# Class_D_Audio_Amplifier_on_TPA3255_ChipD.net
KiCad netlist of a schematic drawn in EasyEDA
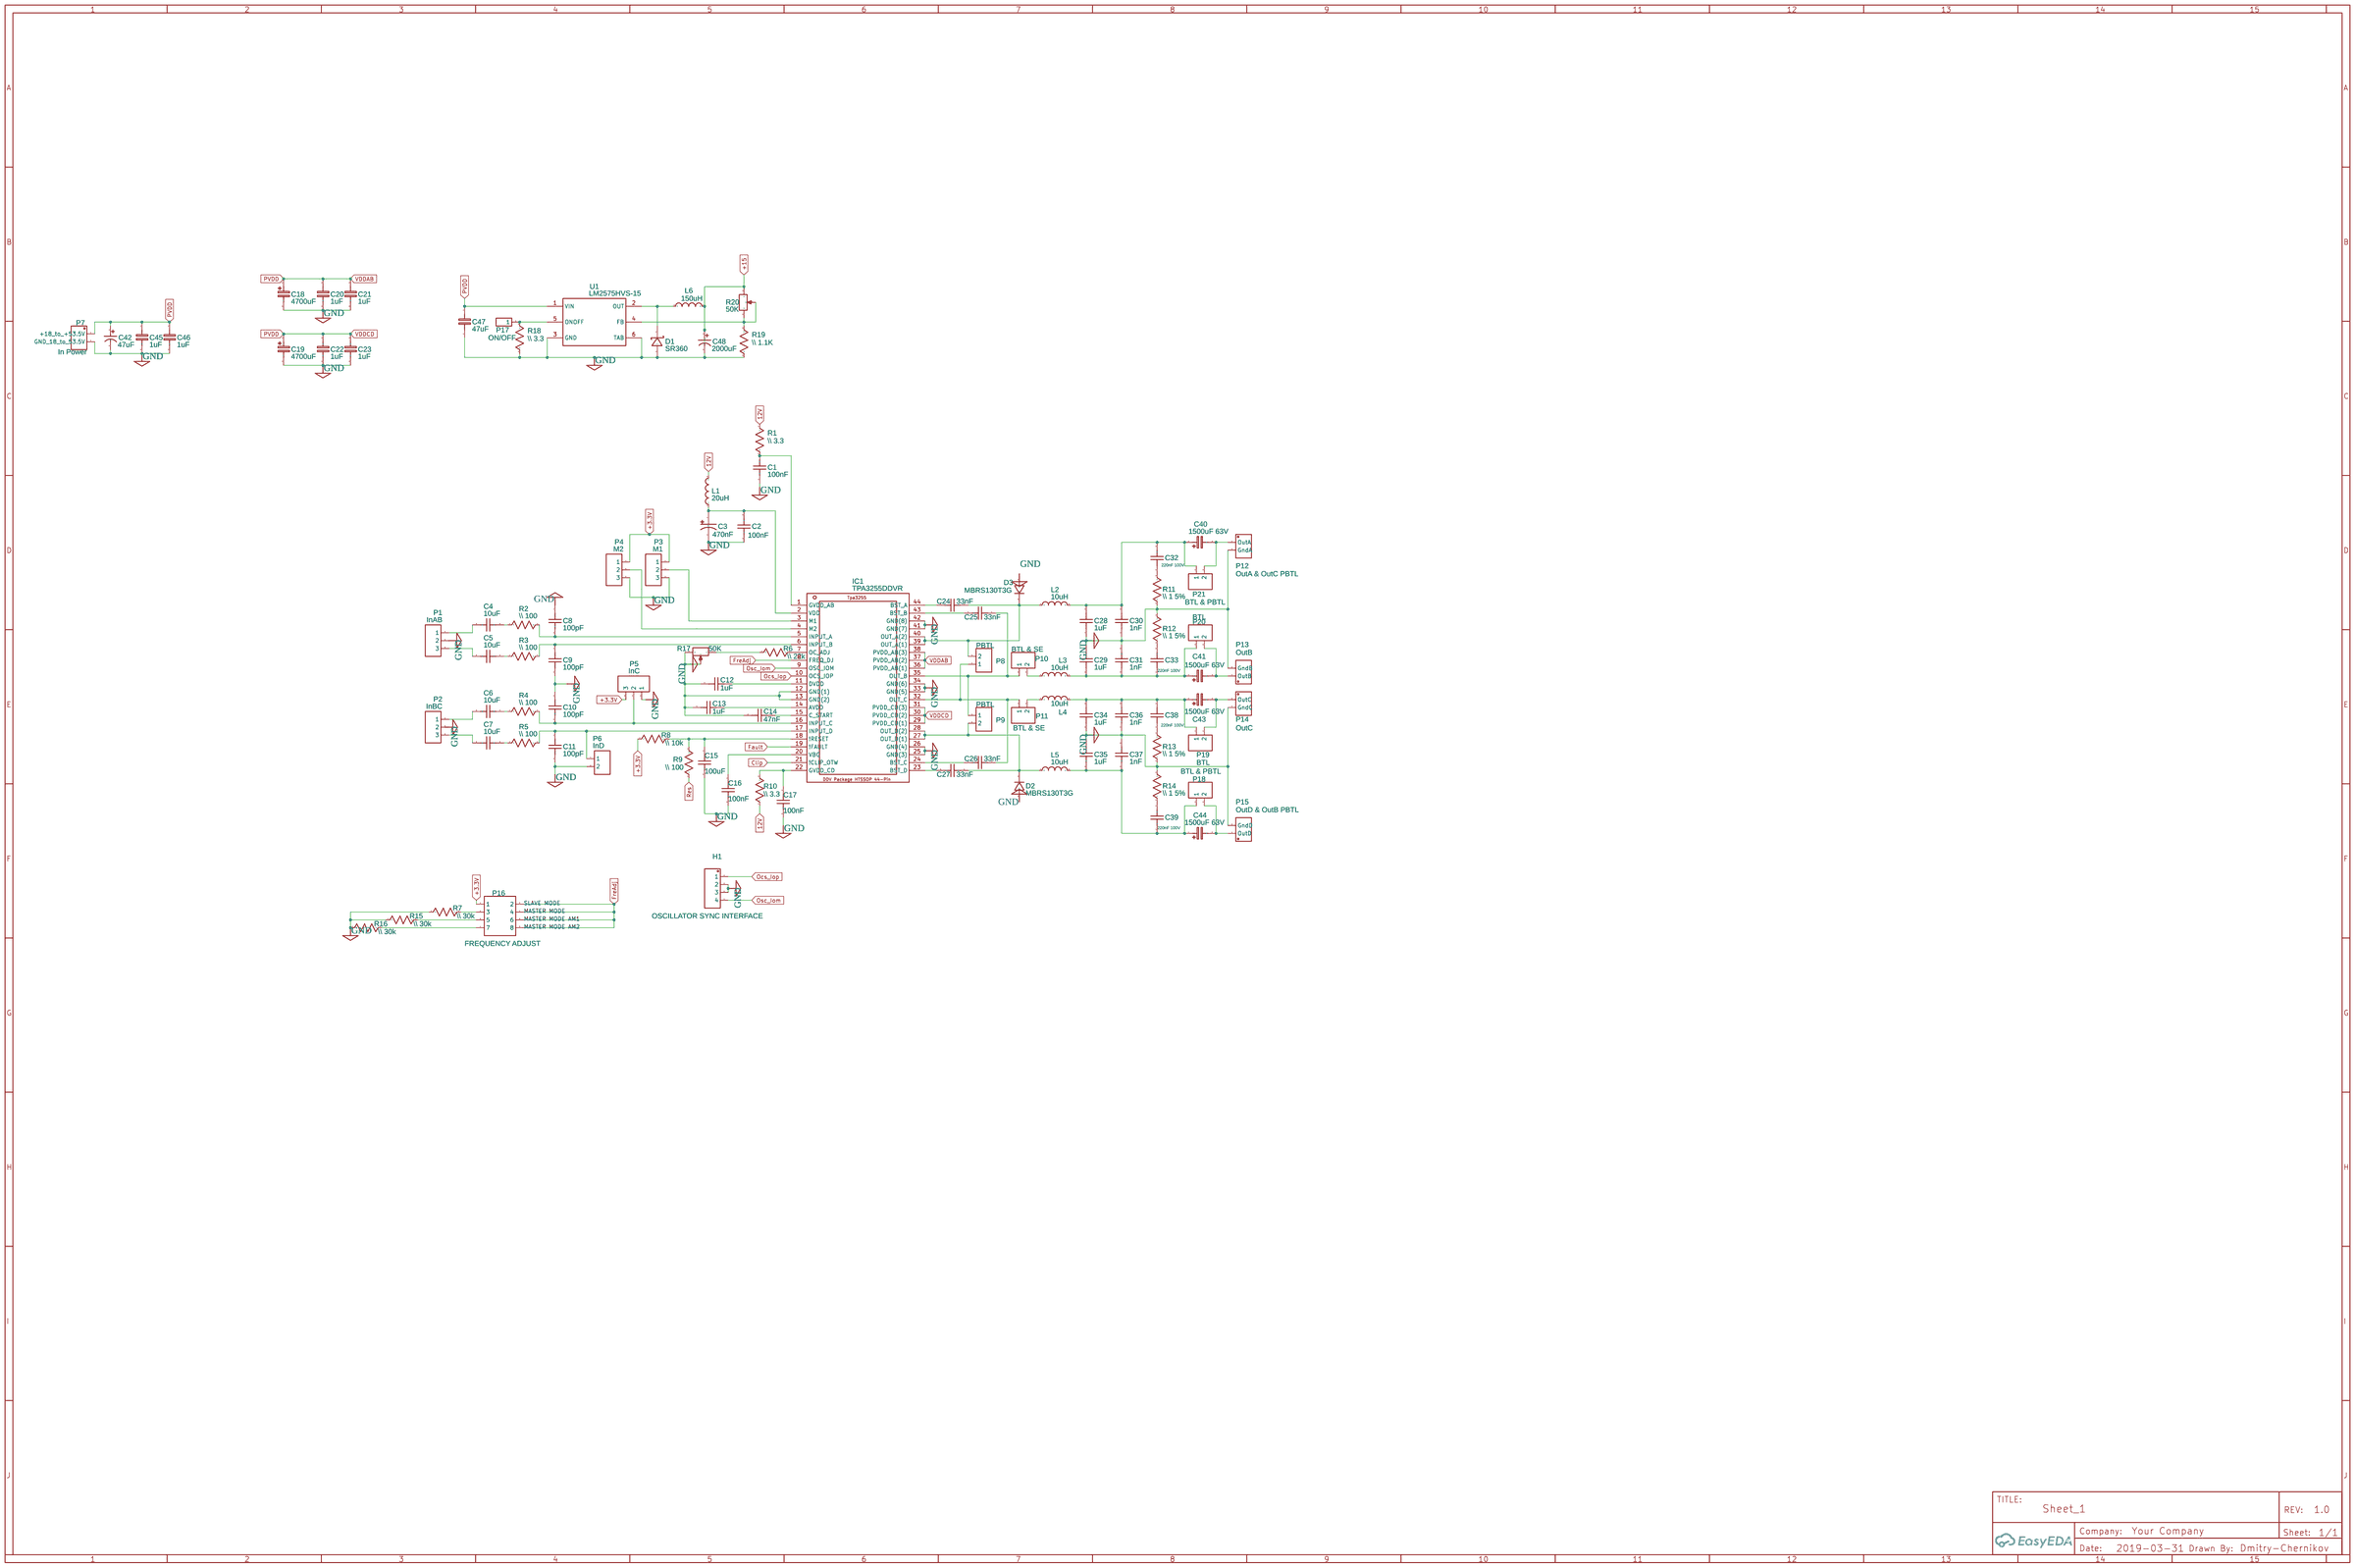
[diagram p0: schematic sheet]

(export (version "E")
  (design (tool "Eeschema 10.0.6"))
  (components
    (comp (ref "C1")
      (value "100nF")
      (fields (field (name "BOM_Manufacturer Part") "?"))
      (libsource (lib "") (part "Cap_RAD-0.2_US_1"))
    )
    (comp (ref "C2")
      (value "100nF")
      (fields (field (name "BOM_Manufacturer Part") "?"))
      (libsource (lib "") (part "Cap_RAD-0.2_US_1"))
    )
    (comp (ref "C3")
      (value "470nF")
      (fields (field (name "BOM_Manufacturer Part") "?"))
      (libsource (lib "") (part "Cap_Electrolytic(TH)_D3.0XF1.5_US"))
    )
    (comp (ref "C4")
      (value "10uF")
      (fields (field (name "BOM_Manufacturer Part") "?"))
      (libsource (lib "") (part "Cap_RAD-0.2_US_2"))
    )
    (comp (ref "C5")
      (value "10uF")
      (fields (field (name "BOM_Manufacturer Part") "?"))
      (libsource (lib "") (part "Cap_RAD-0.2_US_2"))
    )
    (comp (ref "C6")
      (value "10uF")
      (fields (field (name "BOM_Manufacturer Part") "?"))
      (libsource (lib "") (part "Cap_RAD-0.2_US_2"))
    )
    (comp (ref "C7")
      (value "10uF")
      (fields (field (name "BOM_Manufacturer Part") "?"))
      (libsource (lib "") (part "Cap_RAD-0.2_US_2"))
    )
    (comp (ref "C8")
      (value "100pF")
      (fields (field (name "BOM_Manufacturer Part") "?"))
      (libsource (lib "") (part "Cap_RAD-0.2_US"))
    )
    (comp (ref "C9")
      (value "100pF")
      (fields (field (name "BOM_Manufacturer Part") "?"))
      (libsource (lib "") (part "Cap_RAD-0.2_US"))
    )
    (comp (ref "C10")
      (value "100pF")
      (fields (field (name "BOM_Manufacturer Part") "?"))
      (libsource (lib "") (part "Cap_RAD-0.2_US"))
    )
    (comp (ref "C11")
      (value "100pF")
      (fields (field (name "BOM_Manufacturer Part") "?"))
      (libsource (lib "") (part "Cap_RAD-0.2_US"))
    )
    (comp (ref "C12")
      (value "1uF")
      (fields (field (name "BOM_Manufacturer Part") "?"))
      (libsource (lib "") (part "Cap_RAD-0.2_US_2"))
    )
    (comp (ref "C13")
      (value "1uF")
      (fields (field (name "BOM_Manufacturer Part") "?"))
      (libsource (lib "") (part "Cap_RAD-0.2_US_2"))
    )
    (comp (ref "C14")
      (value "47nF")
      (fields (field (name "BOM_Manufacturer Part") "?"))
      (libsource (lib "") (part "Cap_RAD-0.2_US_2"))
    )
    (comp (ref "C15")
      (value "100uF")
      (fields (field (name "BOM_Manufacturer Part") "?"))
      (libsource (lib "") (part "Cap_RAD-0.2_US"))
    )
    (comp (ref "C16")
      (value "100nF")
      (fields (field (name "BOM_Manufacturer Part") "?"))
      (libsource (lib "") (part "Cap_RAD-0.2_US"))
    )
    (comp (ref "C17")
      (value "100nF")
      (fields (field (name "BOM_Manufacturer Part") "?"))
      (libsource (lib "") (part "Cap_RAD-0.2_US"))
    )
    (comp (ref "C18")
      (value "4700uF")
      (fields (field (name "BOM_Manufacturer Part") "?"))
      (libsource (lib "") (part "Cap_Electrolytic(TH)_D8.0XF3.5_EU"))
    )
    (comp (ref "C19")
      (value "4700uF")
      (fields (field (name "BOM_Manufacturer Part") "?"))
      (libsource (lib "") (part "Cap_Electrolytic(TH)_D8.0XF3.5_EU"))
    )
    (comp (ref "C20")
      (value "1uF")
      (fields (field (name "BOM_Manufacturer Part") "?"))
      (libsource (lib "") (part "Cap_1206_EU"))
    )
    (comp (ref "C21")
      (value "1uF")
      (fields (field (name "BOM_Manufacturer Part") "?"))
      (libsource (lib "") (part "Cap_1206_EU"))
    )
    (comp (ref "C22")
      (value "1uF")
      (fields (field (name "BOM_Manufacturer Part") "?"))
      (libsource (lib "") (part "Cap_1206_EU"))
    )
    (comp (ref "C23")
      (value "1uF")
      (fields (field (name "BOM_Manufacturer Part") "?"))
      (libsource (lib "") (part "Cap_1206_EU"))
    )
    (comp (ref "C24")
      (value "33nF")
      (fields (field (name "BOM_Manufacturer Part") "?"))
      (libsource (lib "") (part "Cap_RAD-0.2_US_2"))
    )
    (comp (ref "C25")
      (value "33nF")
      (fields (field (name "BOM_Manufacturer Part") "?"))
      (libsource (lib "") (part "Cap_RAD-0.2_US_2"))
    )
    (comp (ref "C26")
      (value "33nF")
      (fields (field (name "BOM_Manufacturer Part") "?"))
      (libsource (lib "") (part "Cap_RAD-0.2_US_2"))
    )
    (comp (ref "C27")
      (value "33nF")
      (fields (field (name "BOM_Manufacturer Part") "?"))
      (libsource (lib "") (part "Cap_RAD-0.2_US_2"))
    )
    (comp (ref "C28")
      (value "1uF")
      (fields (field (name "BOM_Manufacturer Part") "?"))
      (libsource (lib "") (part "Cap_RAD-0.2_US_1"))
    )
    (comp (ref "C29")
      (value "1uF")
      (fields (field (name "BOM_Manufacturer Part") "?"))
      (libsource (lib "") (part "Cap_RAD-0.2_US_1"))
    )
    (comp (ref "C30")
      (value "1nF")
      (fields (field (name "BOM_Manufacturer Part") "?"))
      (libsource (lib "") (part "Cap_RAD-0.2_US_1"))
    )
    (comp (ref "C31")
      (value "1nF")
      (fields (field (name "BOM_Manufacturer Part") "?"))
      (libsource (lib "") (part "Cap_RAD-0.2_US_1"))
    )
    (comp (ref "C32")
      (value "220nF 100V")
      (fields (field (name "BOM_Manufacturer Part") "?"))
      (libsource (lib "") (part "Cap_RAD-0.2_US_1"))
    )
    (comp (ref "C33")
      (value "220nF 100V")
      (fields (field (name "BOM_Manufacturer Part") "?"))
      (libsource (lib "") (part "Cap_RAD-0.2_US_1"))
    )
    (comp (ref "C34")
      (value "1uF")
      (fields (field (name "BOM_Manufacturer Part") "?"))
      (libsource (lib "") (part "Cap_RAD-0.2_US_1"))
    )
    (comp (ref "C35")
      (value "1uF")
      (fields (field (name "BOM_Manufacturer Part") "?"))
      (libsource (lib "") (part "Cap_RAD-0.2_US_1"))
    )
    (comp (ref "C36")
      (value "1nF")
      (fields (field (name "BOM_Manufacturer Part") "?"))
      (libsource (lib "") (part "Cap_RAD-0.2_US_1"))
    )
    (comp (ref "C37")
      (value "1nF")
      (fields (field (name "BOM_Manufacturer Part") "?"))
      (libsource (lib "") (part "Cap_RAD-0.2_US_1"))
    )
    (comp (ref "C38")
      (value "220nF 100V")
      (fields (field (name "BOM_Manufacturer Part") "?"))
      (libsource (lib "") (part "Cap_RAD-0.2_US_1"))
    )
    (comp (ref "C39")
      (value "220nF 100V")
      (fields (field (name "BOM_Manufacturer Part") "?"))
      (libsource (lib "") (part "Cap_RAD-0.2_US_1"))
    )
    (comp (ref "C40")
      (value "1500uF 63V")
      (fields (field (name "BOM_Manufacturer Part") "?"))
      (libsource (lib "") (part "Cap_Electrolytic(TH)_D8.0XF3.5_EU_1"))
    )
    (comp (ref "C41")
      (value "1500uF 63V")
      (fields (field (name "BOM_Manufacturer Part") "?"))
      (libsource (lib "") (part "Cap_Electrolytic(TH)_D8.0XF3.5_EU_1"))
    )
    (comp (ref "C42")
      (value "47uF")
      (fields
        (field (name "BOM_Manufacturer Part") "47uF 63V 6.3*11")
        (field (name "BOM_Supplier Part") "C45673")
      )
      (libsource (lib "") (part "47uF 63V 6.3*11"))
    )
    (comp (ref "C43")
      (value "1500uF 63V")
      (fields (field (name "BOM_Manufacturer Part") "?"))
      (libsource (lib "") (part "Cap_Electrolytic(TH)_D8.0XF3.5_EU_1"))
    )
    (comp (ref "C44")
      (value "1500uF 63V")
      (fields (field (name "BOM_Manufacturer Part") "?"))
      (libsource (lib "") (part "Cap_Electrolytic(TH)_D8.0XF3.5_EU_2"))
    )
    (comp (ref "C45")
      (value "1uF")
      (fields (field (name "BOM_Manufacturer Part") "?"))
      (libsource (lib "") (part "Cap_1206_EU"))
    )
    (comp (ref "C46")
      (value "1uF")
      (fields (field (name "BOM_Manufacturer Part") "?"))
      (libsource (lib "") (part "Cap_1206_EU"))
    )
    (comp (ref "C47")
      (value "47uF")
      (fields (field (name "BOM_Manufacturer Part") "?"))
      (libsource (lib "") (part "Cap_1206_EU_1"))
    )
    (comp (ref "C48")
      (value "2000uF")
      (fields
        (field (name "BOM_Manufacturer Part") "47uF 63V 6.3*11")
        (field (name "BOM_Supplier Part") "C45673")
      )
      (libsource (lib "") (part "47uF 63V 6.3*11"))
    )
    (comp (ref "D1")
      (value "SR360")
      (fields
        (field (name "BOM_Manufacturer Part") "MBR0520LT1G")
        (field (name "BOM_Supplier Part") "C23848")
      )
      (libsource (lib "") (part "Unknown_830_430"))
    )
    (comp (ref "D2")
      (value "MBRS130T3G")
      (fields (field (name "BOM_Supplier Part") "C146717"))
      (libsource (lib "") (part "Unknown_1290_995"))
    )
    (comp (ref "D3")
      (value "MBRS130T3G")
      (fields (field (name "BOM_Supplier Part") "C146717"))
      (libsource (lib "") (part "Unknown_1290_745"))
    )
    (comp (ref "H1")
      (value "OSCILLATOR SYNC INTERFACE")
      (fields
        (field (name "BOM_Manufacturer Part") "210S-1*4P L=11.6MMGold-plated black")
        (field (name "BOM_Supplier Part") "C124378")
      )
      (libsource (lib "") (part "Unknown_905_1125"))
    )
    (comp (ref "IC1")
      (value "TPA3255DDVR")
      (fields (field (name "BOM_Manufacturer Part") "TPA3255 DDV Package HTSSOP 44-Pin"))
      (libsource (lib "") (part "Unknown_1090_865"))
    )
    (comp (ref "L1")
      (value "20uH")
      (fields (field (name "BOM_Manufacturer Part") "?"))
      (libsource (lib "") (part "Inductor_AXIAL-0.4_US"))
    )
    (comp (ref "L2")
      (value "10uH")
      (fields (field (name "BOM_Manufacturer Part") "?"))
      (libsource (lib "") (part "Inductor_AXIAL-0.6_US"))
    )
    (comp (ref "L3")
      (value "10uH")
      (fields (field (name "BOM_Manufacturer Part") "?"))
      (libsource (lib "") (part "Inductor_AXIAL-0.6_US"))
    )
    (comp (ref "L4")
      (value "10uH")
      (fields (field (name "BOM_Manufacturer Part") "?"))
      (libsource (lib "") (part "Inductor_AXIAL-0.6_US"))
    )
    (comp (ref "L5")
      (value "10uH")
      (fields (field (name "BOM_Manufacturer Part") "?"))
      (libsource (lib "") (part "Inductor_AXIAL-0.6_US"))
    )
    (comp (ref "L6")
      (value "150uH")
      (fields (field (name "BOM_Manufacturer Part") "?"))
      (libsource (lib "") (part "Inductor_AXIAL-0.4_US_1"))
    )
    (comp (ref "P1")
      (value "InAB")
      (fields
        (field (name "BOM_Manufacturer Part") "Header2.54mm 1*3P")
        (field (name "BOM_Supplier Part") "C49257")
      )
      (libsource (lib "") (part "Unknown_550_810"))
    )
    (comp (ref "P2")
      (value "InBC")
      (fields
        (field (name "BOM_Manufacturer Part") "Header2.54mm 1*3P")
        (field (name "BOM_Supplier Part") "C49257")
      )
      (libsource (lib "") (part "Unknown_550_920"))
    )
    (comp (ref "P3")
      (value "M1")
      (fields
        (field (name "BOM_Manufacturer Part") "Header2.54mm 1*3P")
        (field (name "BOM_Supplier Part") "C49257")
      )
      (libsource (lib "") (part "Unknown_830_720"))
    )
    (comp (ref "P4")
      (value "M2")
      (fields
        (field (name "BOM_Manufacturer Part") "Header2.54mm 1*3P")
        (field (name "BOM_Supplier Part") "C49257")
      )
      (libsource (lib "") (part "Unknown_780_720"))
    )
    (comp (ref "P5")
      (value "InC")
      (fields
        (field (name "BOM_Manufacturer Part") "Header2.54mm 1*3P")
        (field (name "BOM_Supplier Part") "C49257")
      )
      (libsource (lib "") (part "Unknown_800_870"))
    )
    (comp (ref "P6")
      (value "InD")
      (fields
        (field (name "BOM_Manufacturer Part") "2.54-1*2PFemale")
        (field (name "BOM_Supplier Part") "C49661")
      )
      (libsource (lib "") (part "Unknown_755_965"))
    )
    (comp (ref "P7")
      (value "In Power")
      (fields
        (field (name "BOM_Manufacturer Part") "WJ2EDGVC-5.08-2P")
        (field (name "BOM_Supplier Part") "C8445")
      )
      (libsource (lib "") (part "Unknown_100_425"))
    )
    (comp (ref "P8")
      (value "PBTL")
      (fields
        (field (name "BOM_Manufacturer Part") "2.54-1*2PFemale")
        (field (name "BOM_Supplier Part") "C49661")
      )
      (libsource (lib "") (part "Unknown_1240_835"))
    )
    (comp (ref "P9")
      (value "PBTL")
      (fields
        (field (name "BOM_Manufacturer Part") "2.54-1*2PFemale")
        (field (name "BOM_Supplier Part") "C49661")
      )
      (libsource (lib "") (part "Unknown_1240_910"))
    )
    (comp (ref "P10")
      (value "BTL & SE")
      (fields
        (field (name "BOM_Manufacturer Part") "2.54-1*2PFemale")
        (field (name "BOM_Supplier Part") "C49661")
      )
      (libsource (lib "") (part "Unknown_1295_840"))
    )
    (comp (ref "P11")
      (value "BTL & SE")
      (fields
        (field (name "BOM_Manufacturer Part") "2.54-1*2PFemale")
        (field (name "BOM_Supplier Part") "C49661")
      )
      (libsource (lib "") (part "Unknown_1295_900"))
    )
    (comp (ref "P12")
      (value "OutA & OutC PBTL")
      (fields
        (field (name "BOM_Manufacturer Part") "WJ2EDGVC-5.08-2P")
        (field (name "BOM_Supplier Part") "C8445")
      )
      (libsource (lib "") (part "Unknown_1570_690"))
    )
    (comp (ref "P13")
      (value "OutB")
      (fields
        (field (name "BOM_Manufacturer Part") "WJ2EDGVC-5.08-2P")
        (field (name "BOM_Supplier Part") "C8445")
      )
      (libsource (lib "") (part "Unknown_1570_850"))
    )
    (comp (ref "P14")
      (value "OutC")
      (fields
        (field (name "BOM_Manufacturer Part") "WJ2EDGVC-5.08-2P")
        (field (name "BOM_Supplier Part") "C8445")
      )
      (libsource (lib "") (part "Unknown_1570_890"))
    )
    (comp (ref "P15")
      (value "OutD & OutB PBTL")
      (fields
        (field (name "BOM_Manufacturer Part") "WJ2EDGVC-5.08-2P")
        (field (name "BOM_Supplier Part") "C8445")
      )
      (libsource (lib "") (part "Unknown_1570_1050"))
    )
    (comp (ref "P16")
      (value "FREQUENCY ADJUST")
      (fields
        (field (name "BOM_Manufacturer Part") "Header2X4P 2.54mm")
        (field (name "BOM_Supplier Part") "C124386")
      )
      (libsource (lib "") (part "Unknown_630_1160"))
    )
    (comp (ref "P17")
      (value "ON/OFF")
      (fields
        (field (name "BOM_Manufacturer Part") "Header-Male-2.54_1x1")
        (field (name "BOM_Supplier Part") "C81276")
      )
      (libsource (lib "") (part "Unknown_640_405"))
    )
    (comp (ref "P18")
      (value "BTL & PBTL")
      (fields
        (field (name "BOM_Manufacturer Part") "2.54-1*2PFemale")
        (field (name "BOM_Supplier Part") "C49661")
      )
      (libsource (lib "") (part "Unknown_1520_1005"))
    )
    (comp (ref "P19")
      (value "BTL")
      (fields
        (field (name "BOM_Manufacturer Part") "2.54-1*2PFemale")
        (field (name "BOM_Supplier Part") "C49661")
      )
      (libsource (lib "") (part "Unknown_1520_935"))
    )
    (comp (ref "P20")
      (value "BTL")
      (fields
        (field (name "BOM_Manufacturer Part") "2.54-1*2PFemale")
        (field (name "BOM_Supplier Part") "C49661")
      )
      (libsource (lib "") (part "Unknown_1520_805"))
    )
    (comp (ref "P21")
      (value "BTL & PBTL")
      (fields
        (field (name "BOM_Manufacturer Part") "2.54-1*2PFemale")
        (field (name "BOM_Supplier Part") "C49661")
      )
      (libsource (lib "") (part "Unknown_1520_730"))
    )
    (comp (ref "R1")
      (value "\\\\ 3.3")
      (fields (field (name "BOM_Manufacturer Part") "?"))
      (libsource (lib "") (part "Res_AXIAL-0.3(1/8W)_US_2"))
    )
    (comp (ref "R2")
      (value "\\\\ 100")
      (fields (field (name "BOM_Manufacturer Part") "?"))
      (libsource (lib "") (part "Res_AXIAL-0.3(1/8W)_US"))
    )
    (comp (ref "R3")
      (value "\\\\ 100")
      (fields (field (name "BOM_Manufacturer Part") "?"))
      (libsource (lib "") (part "Res_AXIAL-0.3(1/8W)_US"))
    )
    (comp (ref "R4")
      (value "\\\\ 100")
      (fields (field (name "BOM_Manufacturer Part") "?"))
      (libsource (lib "") (part "Res_AXIAL-0.3(1/8W)_US"))
    )
    (comp (ref "R5")
      (value "\\\\ 100")
      (fields (field (name "BOM_Manufacturer Part") "?"))
      (libsource (lib "") (part "Res_AXIAL-0.3(1/8W)_US"))
    )
    (comp (ref "R6")
      (value "\\\\ 22k")
      (fields (field (name "BOM_Manufacturer Part") "?"))
      (libsource (lib "") (part "Res_AXIAL-0.3(1/8W)_US"))
    )
    (comp (ref "R7")
      (value "\\\\ 30k")
      (fields (field (name "BOM_Manufacturer Part") "?"))
      (libsource (lib "") (part "Res_AXIAL-0.3(1/8W)_US"))
    )
    (comp (ref "R8")
      (value "\\\\ 10k")
      (fields (field (name "BOM_Manufacturer Part") "?"))
      (libsource (lib "") (part "Res_AXIAL-0.3(1/8W)_US"))
    )
    (comp (ref "R9")
      (value "\\\\ 100")
      (fields (field (name "BOM_Manufacturer Part") "?"))
      (libsource (lib "") (part "Res_AXIAL-0.3(1/8W)_US_1"))
    )
    (comp (ref "R10")
      (value "\\\\ 3.3")
      (fields (field (name "BOM_Manufacturer Part") "?"))
      (libsource (lib "") (part "Res_AXIAL-0.3(1/8W)_US_1"))
    )
    (comp (ref "R11")
      (value "\\\\ 1 5%")
      (fields (field (name "BOM_Manufacturer Part") "?"))
      (libsource (lib "") (part "Res_AXIAL-0.3(1/8W)_US_1"))
    )
    (comp (ref "R12")
      (value "\\\\ 1 5%")
      (fields (field (name "BOM_Manufacturer Part") "?"))
      (libsource (lib "") (part "Res_AXIAL-0.3(1/8W)_US_1"))
    )
    (comp (ref "R13")
      (value "\\\\ 1 5%")
      (fields (field (name "BOM_Manufacturer Part") "?"))
      (libsource (lib "") (part "Res_AXIAL-0.3(1/8W)_US_1"))
    )
    (comp (ref "R14")
      (value "\\\\ 1 5%")
      (fields (field (name "BOM_Manufacturer Part") "?"))
      (libsource (lib "") (part "Res_AXIAL-0.3(1/8W)_US_1"))
    )
    (comp (ref "R15")
      (value "\\\\ 30k")
      (fields (field (name "BOM_Manufacturer Part") "?"))
      (libsource (lib "") (part "Res_AXIAL-0.3(1/8W)_US"))
    )
    (comp (ref "R16")
      (value "\\\\ 30k")
      (fields (field (name "BOM_Manufacturer Part") "?"))
      (libsource (lib "") (part "Res_AXIAL-0.3(1/8W)_US"))
    )
    (comp (ref "R17")
      (value "50K")
      (fields
        (field (name "BOM_Manufacturer Part") "3314J-1-503E")
        (field (name "BOM_Supplier Part") "C50895")
      )
      (libsource (lib "") (part "3314J-1-503E"))
    )
    (comp (ref "R18")
      (value "\\\\ 3.3")
      (fields (field (name "BOM_Manufacturer Part") "?"))
      (libsource (lib "") (part "Res_AXIAL-0.3(1/8W)_US_2"))
    )
    (comp (ref "R19")
      (value "\\\\ 1.1K")
      (fields (field (name "BOM_Manufacturer Part") "?"))
      (libsource (lib "") (part "Res_AXIAL-0.3(1/8W)_US_2"))
    )
    (comp (ref "R20")
      (value "50K")
      (fields
        (field (name "BOM_Manufacturer Part") "3314J-1-503E")
        (field (name "BOM_Supplier Part") "C50895")
      )
      (libsource (lib "") (part "3314J-1-503E_1"))
    )
    (comp (ref "U1")
      (value "LM2575HVS-15")
      (fields (field (name "BOM_Supplier Part") "C62077"))
      (libsource (lib "") (part "Unknown_750_405"))
    )
  )
  (nets
    (net (code "1") (name "+3.3V") (class "Default")
      (node (ref "P16") (pin "1") (pinfunction "1_1") (pintype "input"))
      (node (ref "P3") (pin "1") (pinfunction "1_1") (pintype "input"))
      (node (ref "P4") (pin "1") (pinfunction "1_1") (pintype "input"))
      (node (ref "P5") (pin "3") (pinfunction "3_3") (pintype "input"))
      (node (ref "R8") (pin "1") (pinfunction "1_1") (pintype "unspecified"))
    )
    (net (code "2") (name "+15") (class "Default")
      (node (ref "C48") (pin "1") (pinfunction "1_1") (pintype "input"))
      (node (ref "L6") (pin "2") (pinfunction "2_2") (pintype "unspecified"))
      (node (ref "R20") (pin "1") (pinfunction "1_1") (pintype "input"))
    )
    (net (code "3") (name "12V") (class "Default")
      (node (ref "L1") (pin "2") (pinfunction "2_2") (pintype "unspecified"))
      (node (ref "R1") (pin "1") (pinfunction "1_1") (pintype "unspecified"))
      (node (ref "R10") (pin "1") (pinfunction "1_1") (pintype "unspecified"))
    )
    (net (code "4") (name "Clip") (class "Default")
      (node (ref "IC1") (pin "21") (pinfunction "!CLIP_OTW_21") (pintype "output"))
    )
    (net (code "5") (name "Fault") (class "Default")
      (node (ref "IC1") (pin "19") (pinfunction "!FAULT_19") (pintype "output"))
    )
    (net (code "6") (name "FreAdj") (class "Default")
      (node (ref "IC1") (pin "8") (pinfunction "FREQ_DJ_8") (pintype "output"))
      (node (ref "P16") (pin "2") (pinfunction "2_2") (pintype "input"))
      (node (ref "P16") (pin "4") (pinfunction "4_4") (pintype "input"))
      (node (ref "P16") (pin "6") (pinfunction "6_6") (pintype "input"))
      (node (ref "P16") (pin "8") (pinfunction "8_8") (pintype "input"))
    )
    (net (code "7") (name "GND") (class "Default")
      (node (ref "C1") (pin "1") (pinfunction "1_1") (pintype "unspecified"))
      (node (ref "C10") (pin "1") (pinfunction "1_1") (pintype "unspecified"))
      (node (ref "C11") (pin "2") (pinfunction "2_2") (pintype "unspecified"))
      (node (ref "C12") (pin "2") (pinfunction "2_2") (pintype "unspecified"))
      (node (ref "C13") (pin "2") (pinfunction "2_2") (pintype "unspecified"))
      (node (ref "C14") (pin "2") (pinfunction "2_2") (pintype "unspecified"))
      (node (ref "C15") (pin "2") (pinfunction "2_2") (pintype "unspecified"))
      (node (ref "C16") (pin "2") (pinfunction "2_2") (pintype "unspecified"))
      (node (ref "C17") (pin "2") (pinfunction "2_2") (pintype "unspecified"))
      (node (ref "C18") (pin "2") (pinfunction "2_2") (pintype "unspecified"))
      (node (ref "C19") (pin "2") (pinfunction "2_2") (pintype "unspecified"))
      (node (ref "C2") (pin "1") (pinfunction "1_1") (pintype "unspecified"))
      (node (ref "C20") (pin "2") (pinfunction "2_2") (pintype "unspecified"))
      (node (ref "C21") (pin "2") (pinfunction "2_2") (pintype "unspecified"))
      (node (ref "C22") (pin "2") (pinfunction "2_2") (pintype "unspecified"))
      (node (ref "C23") (pin "2") (pinfunction "2_2") (pintype "unspecified"))
      (node (ref "C28") (pin "1") (pinfunction "1_1") (pintype "unspecified"))
      (node (ref "C29") (pin "2") (pinfunction "2_2") (pintype "unspecified"))
      (node (ref "C3") (pin "2") (pinfunction "2_2") (pintype "unspecified"))
      (node (ref "C30") (pin "1") (pinfunction "1_1") (pintype "unspecified"))
      (node (ref "C31") (pin "2") (pinfunction "2_2") (pintype "unspecified"))
      (node (ref "C34") (pin "1") (pinfunction "1_1") (pintype "unspecified"))
      (node (ref "C35") (pin "2") (pinfunction "2_2") (pintype "unspecified"))
      (node (ref "C36") (pin "1") (pinfunction "1_1") (pintype "unspecified"))
      (node (ref "C37") (pin "2") (pinfunction "2_2") (pintype "unspecified"))
      (node (ref "C42") (pin "2") (pinfunction "2_2") (pintype "input"))
      (node (ref "C45") (pin "2") (pinfunction "2_2") (pintype "unspecified"))
      (node (ref "C46") (pin "2") (pinfunction "2_2") (pintype "unspecified"))
      (node (ref "C47") (pin "2") (pinfunction "2_2") (pintype "unspecified"))
      (node (ref "C48") (pin "2") (pinfunction "2_2") (pintype "input"))
      (node (ref "C8") (pin "1") (pinfunction "1_1") (pintype "unspecified"))
      (node (ref "C9") (pin "2") (pinfunction "2_2") (pintype "unspecified"))
      (node (ref "D1") (pin "1") (pinfunction "A_1") (pintype "unspecified"))
      (node (ref "D2") (pin "1") (pinfunction "1_1") (pintype "unspecified"))
      (node (ref "D3") (pin "1") (pinfunction "1_1") (pintype "unspecified"))
      (node (ref "H1") (pin "2") (pinfunction "2_2") (pintype "unspecified"))
      (node (ref "H1") (pin "3") (pinfunction "3_3") (pintype "unspecified"))
      (node (ref "IC1") (pin "12") (pinfunction "GND(1)_12") (pintype "passive"))
      (node (ref "IC1") (pin "13") (pinfunction "GND(2)_13") (pintype "passive"))
      (node (ref "IC1") (pin "25") (pinfunction "GND(3)_25") (pintype "passive"))
      (node (ref "IC1") (pin "26") (pinfunction "GND(4)_26") (pintype "passive"))
      (node (ref "IC1") (pin "33") (pinfunction "GND(5)_33") (pintype "passive"))
      (node (ref "IC1") (pin "34") (pinfunction "GND(6)_34") (pintype "passive"))
      (node (ref "IC1") (pin "41") (pinfunction "GND(7)_41") (pintype "passive"))
      (node (ref "IC1") (pin "42") (pinfunction "GND(8)_42") (pintype "passive"))
      (node (ref "P1") (pin "2") (pinfunction "2_2") (pintype "input"))
      (node (ref "P12") (pin "2") (pinfunction "GndA_2") (pintype "unspecified"))
      (node (ref "P13") (pin "2") (pinfunction "GndB_2") (pintype "unspecified"))
      (node (ref "P14") (pin "2") (pinfunction "GndC_2") (pintype "unspecified"))
      (node (ref "P15") (pin "2") (pinfunction "GndD_2") (pintype "unspecified"))
      (node (ref "P2") (pin "2") (pinfunction "2_2") (pintype "input"))
      (node (ref "P3") (pin "3") (pinfunction "3_3") (pintype "input"))
      (node (ref "P4") (pin "3") (pinfunction "3_3") (pintype "input"))
      (node (ref "P5") (pin "1") (pinfunction "1_1") (pintype "input"))
      (node (ref "P6") (pin "2") (pinfunction "2_2") (pintype "input"))
      (node (ref "P7") (pin "2") (pinfunction "GND_18_to_53.5V_2") (pintype "unspecified"))
      (node (ref "R11") (pin "1") (pinfunction "1_1") (pintype "unspecified"))
      (node (ref "R12") (pin "2") (pinfunction "2_2") (pintype "unspecified"))
      (node (ref "R13") (pin "1") (pinfunction "1_1") (pintype "unspecified"))
      (node (ref "R14") (pin "2") (pinfunction "2_2") (pintype "unspecified"))
      (node (ref "R15") (pin "1") (pinfunction "1_1") (pintype "unspecified"))
      (node (ref "R16") (pin "1") (pinfunction "1_1") (pintype "unspecified"))
      (node (ref "R17") (pin "2") (pinfunction "2_2") (pintype "input"))
      (node (ref "R17") (pin "3") (pinfunction "3_3") (pintype "input"))
      (node (ref "R18") (pin "2") (pinfunction "2_2") (pintype "unspecified"))
      (node (ref "R19") (pin "2") (pinfunction "2_2") (pintype "unspecified"))
      (node (ref "R7") (pin "1") (pinfunction "1_1") (pintype "unspecified"))
      (node (ref "U1") (pin "3") (pinfunction "GND_3") (pintype "passive"))
      (node (ref "U1") (pin "6") (pinfunction "TAB_6") (pintype "passive"))
    )
    (net (code "8") (name "Net-(C4-Pad1)") (class "Default")
      (node (ref "C4") (pin "1") (pinfunction "1_1") (pintype "unspecified"))
      (node (ref "R2") (pin "1") (pinfunction "1_1") (pintype "unspecified"))
    )
    (net (code "9") (name "Net-(C4-Pad2)") (class "Default")
      (node (ref "C4") (pin "2") (pinfunction "2_2") (pintype "unspecified"))
      (node (ref "P1") (pin "1") (pinfunction "1_1") (pintype "input"))
    )
    (net (code "10") (name "Net-(C5-Pad1)") (class "Default")
      (node (ref "C5") (pin "1") (pinfunction "1_1") (pintype "unspecified"))
      (node (ref "R3") (pin "1") (pinfunction "1_1") (pintype "unspecified"))
    )
    (net (code "11") (name "Net-(C5-Pad2)") (class "Default")
      (node (ref "C5") (pin "2") (pinfunction "2_2") (pintype "unspecified"))
      (node (ref "P1") (pin "3") (pinfunction "3_3") (pintype "input"))
    )
    (net (code "12") (name "Net-(C6-Pad1)") (class "Default")
      (node (ref "C6") (pin "1") (pinfunction "1_1") (pintype "unspecified"))
      (node (ref "R4") (pin "1") (pinfunction "1_1") (pintype "unspecified"))
    )
    (net (code "13") (name "Net-(C6-Pad2)") (class "Default")
      (node (ref "C6") (pin "2") (pinfunction "2_2") (pintype "unspecified"))
      (node (ref "P2") (pin "1") (pinfunction "1_1") (pintype "input"))
    )
    (net (code "14") (name "Net-(C7-Pad1)") (class "Default")
      (node (ref "C7") (pin "1") (pinfunction "1_1") (pintype "unspecified"))
      (node (ref "R5") (pin "1") (pinfunction "1_1") (pintype "unspecified"))
    )
    (net (code "15") (name "Net-(C7-Pad2)") (class "Default")
      (node (ref "C7") (pin "2") (pinfunction "2_2") (pintype "unspecified"))
      (node (ref "P2") (pin "3") (pinfunction "3_3") (pintype "input"))
    )
    (net (code "16") (name "Net-(C28-Pad2)") (class "Default")
      (node (ref "C28") (pin "2") (pinfunction "2_2") (pintype "unspecified"))
      (node (ref "C30") (pin "2") (pinfunction "2_2") (pintype "unspecified"))
      (node (ref "C32") (pin "2") (pinfunction "2_2") (pintype "unspecified"))
      (node (ref "C40") (pin "1") (pinfunction "1_1") (pintype "unspecified"))
      (node (ref "L2") (pin "2") (pinfunction "2_2") (pintype "unspecified"))
      (node (ref "P21") (pin "1") (pinfunction "1_1") (pintype "input"))
    )
    (net (code "17") (name "Net-(C29-Pad1)") (class "Default")
      (node (ref "C29") (pin "1") (pinfunction "1_1") (pintype "unspecified"))
      (node (ref "C31") (pin "1") (pinfunction "1_1") (pintype "unspecified"))
      (node (ref "C33") (pin "1") (pinfunction "1_1") (pintype "unspecified"))
      (node (ref "C41") (pin "1") (pinfunction "1_1") (pintype "unspecified"))
      (node (ref "L3") (pin "2") (pinfunction "2_2") (pintype "unspecified"))
      (node (ref "P20") (pin "1") (pinfunction "1_1") (pintype "input"))
    )
    (net (code "18") (name "Net-(C32-Pad1)") (class "Default")
      (node (ref "C32") (pin "1") (pinfunction "1_1") (pintype "unspecified"))
      (node (ref "R11") (pin "2") (pinfunction "2_2") (pintype "unspecified"))
    )
    (net (code "19") (name "Net-(C33-Pad2)") (class "Default")
      (node (ref "C33") (pin "2") (pinfunction "2_2") (pintype "unspecified"))
      (node (ref "R12") (pin "1") (pinfunction "1_1") (pintype "unspecified"))
    )
    (net (code "20") (name "Net-(C34-Pad2)") (class "Default")
      (node (ref "C34") (pin "2") (pinfunction "2_2") (pintype "unspecified"))
      (node (ref "C36") (pin "2") (pinfunction "2_2") (pintype "unspecified"))
      (node (ref "C38") (pin "2") (pinfunction "2_2") (pintype "unspecified"))
      (node (ref "C43") (pin "1") (pinfunction "1_1") (pintype "unspecified"))
      (node (ref "L4") (pin "2") (pinfunction "2_2") (pintype "unspecified"))
      (node (ref "P19") (pin "1") (pinfunction "1_1") (pintype "input"))
    )
    (net (code "21") (name "Net-(C35-Pad1)") (class "Default")
      (node (ref "C35") (pin "1") (pinfunction "1_1") (pintype "unspecified"))
      (node (ref "C37") (pin "1") (pinfunction "1_1") (pintype "unspecified"))
      (node (ref "C39") (pin "1") (pinfunction "1_1") (pintype "unspecified"))
      (node (ref "C44") (pin "1") (pinfunction "1_1") (pintype "unspecified"))
      (node (ref "L5") (pin "2") (pinfunction "2_2") (pintype "unspecified"))
      (node (ref "P18") (pin "1") (pinfunction "1_1") (pintype "input"))
    )
    (net (code "22") (name "Net-(C38-Pad1)") (class "Default")
      (node (ref "C38") (pin "1") (pinfunction "1_1") (pintype "unspecified"))
      (node (ref "R13") (pin "2") (pinfunction "2_2") (pintype "unspecified"))
    )
    (net (code "23") (name "Net-(C39-Pad2)") (class "Default")
      (node (ref "C39") (pin "2") (pinfunction "2_2") (pintype "unspecified"))
      (node (ref "R14") (pin "1") (pinfunction "1_1") (pintype "unspecified"))
    )
    (net (code "24") (name "Net-(D1-K)") (class "Default")
      (node (ref "D1") (pin "2") (pinfunction "K_2") (pintype "unspecified"))
      (node (ref "L6") (pin "1") (pinfunction "1_1") (pintype "unspecified"))
      (node (ref "U1") (pin "2") (pinfunction "OUT_2") (pintype "passive"))
    )
    (net (code "25") (name "Net-(IC1-!RESET)") (class "Default")
      (node (ref "C15") (pin "1") (pinfunction "1_1") (pintype "unspecified"))
      (node (ref "IC1") (pin "18") (pinfunction "!RESET_18") (pintype "input"))
      (node (ref "R8") (pin "2") (pinfunction "2_2") (pintype "unspecified"))
      (node (ref "R9") (pin "2") (pinfunction "2_2") (pintype "unspecified"))
    )
    (net (code "26") (name "Net-(IC1-AVDD)") (class "Default")
      (node (ref "C13") (pin "1") (pinfunction "1_1") (pintype "unspecified"))
      (node (ref "IC1") (pin "14") (pinfunction "AVDD_14") (pintype "passive"))
    )
    (net (code "27") (name "Net-(IC1-BST_A)") (class "Default")
      (node (ref "C24") (pin "2") (pinfunction "2_2") (pintype "unspecified"))
      (node (ref "IC1") (pin "44") (pinfunction "BST_A_44") (pintype "passive"))
    )
    (net (code "28") (name "Net-(IC1-BST_B)") (class "Default")
      (node (ref "C25") (pin "2") (pinfunction "2_2") (pintype "unspecified"))
      (node (ref "IC1") (pin "43") (pinfunction "BST_B_43") (pintype "passive"))
    )
    (net (code "29") (name "Net-(IC1-BST_C)") (class "Default")
      (node (ref "C26") (pin "2") (pinfunction "2_2") (pintype "unspecified"))
      (node (ref "IC1") (pin "24") (pinfunction "BST_C_24") (pintype "passive"))
    )
    (net (code "30") (name "Net-(IC1-BST_D)") (class "Default")
      (node (ref "C27") (pin "2") (pinfunction "2_2") (pintype "unspecified"))
      (node (ref "IC1") (pin "23") (pinfunction "BST_D_23") (pintype "passive"))
    )
    (net (code "31") (name "Net-(IC1-C_START)") (class "Default")
      (node (ref "C14") (pin "1") (pinfunction "1_1") (pintype "unspecified"))
      (node (ref "IC1") (pin "15") (pinfunction "C_START_15") (pintype "output"))
    )
    (net (code "32") (name "Net-(IC1-DVDD)") (class "Default")
      (node (ref "C12") (pin "1") (pinfunction "1_1") (pintype "unspecified"))
      (node (ref "IC1") (pin "11") (pinfunction "DVDD_11") (pintype "passive"))
    )
    (net (code "33") (name "Net-(IC1-GVDD_AB)") (class "Default")
      (node (ref "C1") (pin "2") (pinfunction "2_2") (pintype "unspecified"))
      (node (ref "IC1") (pin "1") (pinfunction "GVDD_AB_1") (pintype "passive"))
      (node (ref "R1") (pin "2") (pinfunction "2_2") (pintype "unspecified"))
    )
    (net (code "34") (name "Net-(IC1-GVDD_CD)") (class "Default")
      (node (ref "C17") (pin "1") (pinfunction "1_1") (pintype "unspecified"))
      (node (ref "IC1") (pin "22") (pinfunction "GVDD_CD_22") (pintype "passive"))
      (node (ref "R10") (pin "2") (pinfunction "2_2") (pintype "unspecified"))
    )
    (net (code "35") (name "Net-(IC1-INPUT_A)") (class "Default")
      (node (ref "C8") (pin "2") (pinfunction "2_2") (pintype "unspecified"))
      (node (ref "IC1") (pin "5") (pinfunction "INPUT_A_5") (pintype "input"))
      (node (ref "R2") (pin "2") (pinfunction "2_2") (pintype "unspecified"))
    )
    (net (code "36") (name "Net-(IC1-INPUT_B)") (class "Default")
      (node (ref "C9") (pin "1") (pinfunction "1_1") (pintype "unspecified"))
      (node (ref "IC1") (pin "6") (pinfunction "INPUT_B_6") (pintype "input"))
      (node (ref "R3") (pin "2") (pinfunction "2_2") (pintype "unspecified"))
    )
    (net (code "37") (name "Net-(IC1-INPUT_C)") (class "Default")
      (node (ref "C10") (pin "2") (pinfunction "2_2") (pintype "unspecified"))
      (node (ref "IC1") (pin "16") (pinfunction "INPUT_C_16") (pintype "input"))
      (node (ref "P5") (pin "2") (pinfunction "2_2") (pintype "input"))
      (node (ref "R4") (pin "2") (pinfunction "2_2") (pintype "unspecified"))
    )
    (net (code "38") (name "Net-(IC1-INPUT_D)") (class "Default")
      (node (ref "C11") (pin "1") (pinfunction "1_1") (pintype "unspecified"))
      (node (ref "IC1") (pin "17") (pinfunction "INPUT_D_17") (pintype "input"))
      (node (ref "P6") (pin "1") (pinfunction "1_1") (pintype "input"))
      (node (ref "R5") (pin "2") (pinfunction "2_2") (pintype "unspecified"))
    )
    (net (code "39") (name "Net-(IC1-M1)") (class "Default")
      (node (ref "IC1") (pin "3") (pinfunction "M1_3") (pintype "input"))
      (node (ref "P3") (pin "2") (pinfunction "2_2") (pintype "input"))
    )
    (net (code "40") (name "Net-(IC1-M2)") (class "Default")
      (node (ref "IC1") (pin "4") (pinfunction "M2_4") (pintype "input"))
      (node (ref "P4") (pin "2") (pinfunction "2_2") (pintype "input"))
    )
    (net (code "41") (name "Net-(IC1-OC_ADJ)") (class "Default")
      (node (ref "IC1") (pin "7") (pinfunction "OC_ADJ_7") (pintype "bidirectional"))
      (node (ref "R6") (pin "2") (pinfunction "2_2") (pintype "unspecified"))
    )
    (net (code "42") (name "Net-(IC1-OUT_A(1))") (class "Default")
      (node (ref "C24") (pin "1") (pinfunction "1_1") (pintype "unspecified"))
      (node (ref "D3") (pin "2") (pinfunction "2_2") (pintype "unspecified"))
      (node (ref "IC1") (pin "39") (pinfunction "OUT_A(1)_39") (pintype "output"))
      (node (ref "IC1") (pin "40") (pinfunction "OUT_A(2)_40") (pintype "output"))
      (node (ref "L2") (pin "1") (pinfunction "1_1") (pintype "unspecified"))
      (node (ref "P8") (pin "2") (pinfunction "2_2") (pintype "input"))
    )
    (net (code "43") (name "Net-(IC1-OUT_B)") (class "Default")
      (node (ref "C25") (pin "1") (pinfunction "1_1") (pintype "unspecified"))
      (node (ref "IC1") (pin "35") (pinfunction "OUT_B_35") (pintype "output"))
      (node (ref "P10") (pin "1") (pinfunction "1_1") (pintype "input"))
      (node (ref "P9") (pin "1") (pinfunction "1_1") (pintype "input"))
    )
    (net (code "44") (name "Net-(IC1-OUT_C)") (class "Default")
      (node (ref "C26") (pin "1") (pinfunction "1_1") (pintype "unspecified"))
      (node (ref "IC1") (pin "32") (pinfunction "OUT_C_32") (pintype "output"))
      (node (ref "P11") (pin "1") (pinfunction "1_1") (pintype "input"))
      (node (ref "P8") (pin "1") (pinfunction "1_1") (pintype "input"))
    )
    (net (code "45") (name "Net-(IC1-OUT_D(1))") (class "Default")
      (node (ref "C27") (pin "1") (pinfunction "1_1") (pintype "unspecified"))
      (node (ref "D2") (pin "2") (pinfunction "2_2") (pintype "unspecified"))
      (node (ref "IC1") (pin "27") (pinfunction "OUT_D(1)_27") (pintype "output"))
      (node (ref "IC1") (pin "28") (pinfunction "OUT_D(2)_28") (pintype "output"))
      (node (ref "L5") (pin "1") (pinfunction "1_1") (pintype "unspecified"))
      (node (ref "P9") (pin "2") (pinfunction "2_2") (pintype "input"))
    )
    (net (code "46") (name "Net-(IC1-VBG)") (class "Default")
      (node (ref "C16") (pin "1") (pinfunction "1_1") (pintype "unspecified"))
      (node (ref "IC1") (pin "20") (pinfunction "VBG_20") (pintype "passive"))
    )
    (net (code "47") (name "Net-(IC1-VDD)") (class "Default")
      (node (ref "C2") (pin "2") (pinfunction "2_2") (pintype "unspecified"))
      (node (ref "C3") (pin "1") (pinfunction "1_1") (pintype "unspecified"))
      (node (ref "IC1") (pin "2") (pinfunction "VDD_2") (pintype "passive"))
      (node (ref "L1") (pin "1") (pinfunction "1_1") (pintype "unspecified"))
    )
    (net (code "48") (name "Net-(L3-Pad1)") (class "Default")
      (node (ref "L3") (pin "1") (pinfunction "1_1") (pintype "unspecified"))
      (node (ref "P10") (pin "2") (pinfunction "2_2") (pintype "input"))
    )
    (net (code "49") (name "Net-(L4-Pad1)") (class "Default")
      (node (ref "L4") (pin "1") (pinfunction "1_1") (pintype "unspecified"))
      (node (ref "P11") (pin "2") (pinfunction "2_2") (pintype "input"))
    )
    (net (code "50") (name "Net-(P12-OutA)") (class "Default")
      (node (ref "C40") (pin "2") (pinfunction "2_2") (pintype "unspecified"))
      (node (ref "P12") (pin "1") (pinfunction "OutA_1") (pintype "unspecified"))
      (node (ref "P21") (pin "2") (pinfunction "2_2") (pintype "input"))
    )
    (net (code "51") (name "Net-(P13-OutB)") (class "Default")
      (node (ref "C41") (pin "2") (pinfunction "2_2") (pintype "unspecified"))
      (node (ref "P13") (pin "1") (pinfunction "OutB_1") (pintype "unspecified"))
      (node (ref "P20") (pin "2") (pinfunction "2_2") (pintype "input"))
    )
    (net (code "52") (name "Net-(P14-OutC)") (class "Default")
      (node (ref "C43") (pin "2") (pinfunction "2_2") (pintype "unspecified"))
      (node (ref "P14") (pin "1") (pinfunction "OutC_1") (pintype "unspecified"))
      (node (ref "P19") (pin "2") (pinfunction "2_2") (pintype "input"))
    )
    (net (code "53") (name "Net-(P15-OutD)") (class "Default")
      (node (ref "C44") (pin "2") (pinfunction "2_2") (pintype "unspecified"))
      (node (ref "P15") (pin "1") (pinfunction "OutD_1") (pintype "unspecified"))
      (node (ref "P18") (pin "2") (pinfunction "2_2") (pintype "input"))
    )
    (net (code "54") (name "Net-(P16-Pad3)") (class "Default")
      (node (ref "P16") (pin "3") (pinfunction "3_3") (pintype "input"))
      (node (ref "R7") (pin "2") (pinfunction "2_2") (pintype "unspecified"))
    )
    (net (code "55") (name "Net-(P16-Pad5)") (class "Default")
      (node (ref "P16") (pin "5") (pinfunction "5_5") (pintype "input"))
      (node (ref "R15") (pin "2") (pinfunction "2_2") (pintype "unspecified"))
    )
    (net (code "56") (name "Net-(P16-Pad7)") (class "Default")
      (node (ref "P16") (pin "7") (pinfunction "7_7") (pintype "input"))
      (node (ref "R16") (pin "2") (pinfunction "2_2") (pintype "unspecified"))
    )
    (net (code "57") (name "Net-(R17-Pad1)") (class "Default")
      (node (ref "R17") (pin "1") (pinfunction "1_1") (pintype "input"))
      (node (ref "R6") (pin "1") (pinfunction "1_1") (pintype "unspecified"))
    )
    (net (code "58") (name "Net-(U1-FB)") (class "Default")
      (node (ref "R19") (pin "1") (pinfunction "1_1") (pintype "unspecified"))
      (node (ref "R20") (pin "2") (pinfunction "2_2") (pintype "input"))
      (node (ref "R20") (pin "3") (pinfunction "3_3") (pintype "input"))
      (node (ref "U1") (pin "4") (pinfunction "FB_4") (pintype "unspecified"))
    )
    (net (code "59") (name "Net-(U1-ONOFF)") (class "Default")
      (node (ref "P17") (pin "1") (pinfunction "1_1") (pintype "input"))
      (node (ref "R18") (pin "1") (pinfunction "1_1") (pintype "unspecified"))
      (node (ref "U1") (pin "5") (pinfunction "ONOFF_5") (pintype "unspecified"))
    )
    (net (code "60") (name "Ocs_Iop") (class "Default")
      (node (ref "H1") (pin "1") (pinfunction "1_1") (pintype "unspecified"))
      (node (ref "IC1") (pin "10") (pinfunction "OCS_IOP_10") (pintype "output"))
    )
    (net (code "61") (name "Osc_Iom") (class "Default")
      (node (ref "H1") (pin "4") (pinfunction "4_4") (pintype "unspecified"))
      (node (ref "IC1") (pin "9") (pinfunction "OSC_IOM_9") (pintype "bidirectional"))
    )
    (net (code "62") (name "PVDD") (class "Default")
      (node (ref "C18") (pin "1") (pinfunction "1_1") (pintype "unspecified"))
      (node (ref "C19") (pin "1") (pinfunction "1_1") (pintype "unspecified"))
      (node (ref "C20") (pin "1") (pinfunction "1_1") (pintype "unspecified"))
      (node (ref "C21") (pin "1") (pinfunction "1_1") (pintype "unspecified"))
      (node (ref "C22") (pin "1") (pinfunction "1_1") (pintype "unspecified"))
      (node (ref "C23") (pin "1") (pinfunction "1_1") (pintype "unspecified"))
      (node (ref "C42") (pin "1") (pinfunction "1_1") (pintype "input"))
      (node (ref "C45") (pin "1") (pinfunction "1_1") (pintype "unspecified"))
      (node (ref "C46") (pin "1") (pinfunction "1_1") (pintype "unspecified"))
      (node (ref "C47") (pin "1") (pinfunction "1_1") (pintype "unspecified"))
      (node (ref "IC1") (pin "29") (pinfunction "PVDD_CD(1)_29") (pintype "passive"))
      (node (ref "IC1") (pin "30") (pinfunction "PVDD_CD(2)_30") (pintype "passive"))
      (node (ref "IC1") (pin "31") (pinfunction "PVDD_CD(3)_31") (pintype "passive"))
      (node (ref "IC1") (pin "36") (pinfunction "PVDD_AB(1)_36") (pintype "passive"))
      (node (ref "IC1") (pin "37") (pinfunction "PVDD_AB(2)_37") (pintype "passive"))
      (node (ref "IC1") (pin "38") (pinfunction "PVDD_AB(3)_38") (pintype "passive"))
      (node (ref "P7") (pin "1") (pinfunction "+18_to_+53.5V_1") (pintype "unspecified"))
      (node (ref "U1") (pin "1") (pinfunction "VIN_1") (pintype "passive"))
    )
    (net (code "63") (name "Res") (class "Default")
      (node (ref "R9") (pin "1") (pinfunction "1_1") (pintype "unspecified"))
    )
  )
)
